# SD.net
KiCad netlist of a schematic drawn in Altium Designer
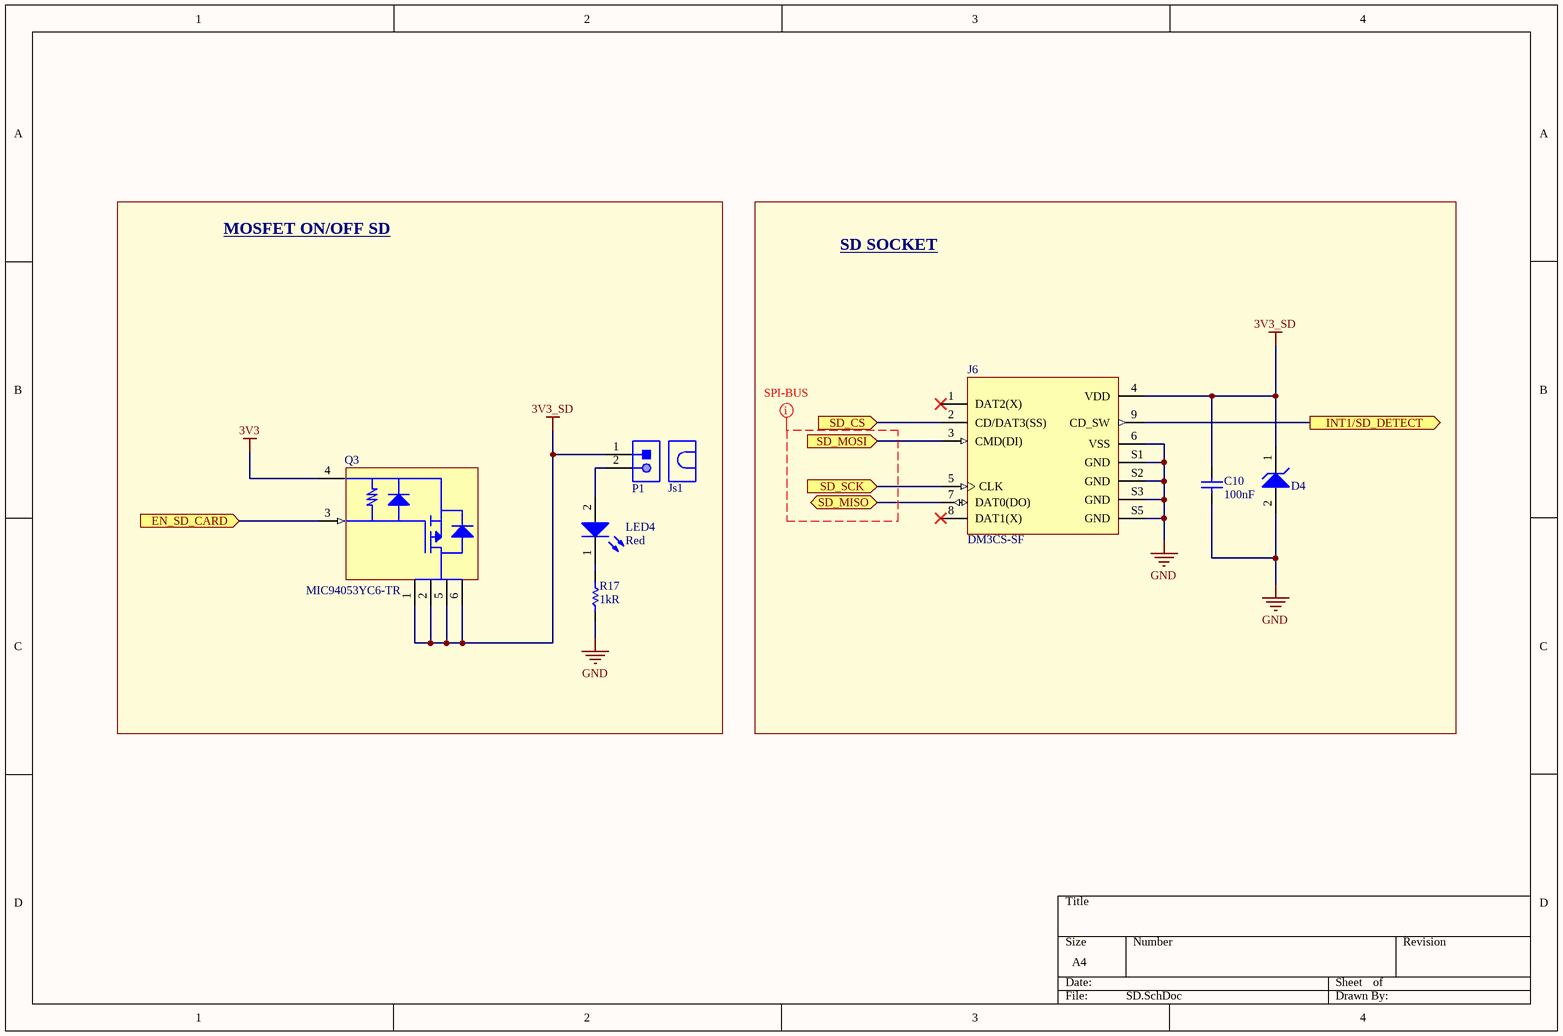
[diagram p0: SD.SchDoc]

(export (version "E")
  (design (tool "Eeschema 10.0.6"))
  (components
    (comp (ref "C10")
      (value "100nF")
      (footprint "Cap 0805 (2012 Metric)")
      (fields
        (field (name "MANUFACTURER") "Yageo")
        (field (name "MANUFACTURER PART NUMBER") "CC0805ZRY5V9BB104")
        (field (name "TOLERANCE") "80%")
      )
      (libsource (lib "Daniel_Integrated_Library") (part "Capacitor"))
    )
    (comp (ref "D4")
      (value "Diode")
      (footprint "Diode SOD123")
      (description "DIODE GEN PURP 75V 150MA 0603")
      (fields
        (field (name "MANUFACTURER") "Taiwan Semiconductor")
        (field (name "MANUFACTURER PART NUMBER") "TS4148CRZG")
      )
      (libsource (lib "Daniel_Integrated_Library") (part "Diode"))
    )
    (comp (ref "J6")
      (value "DM3CS-SF")
      (footprint "SDHolder")
      (description "10 (8 + 2) Position Card Connector Secure Digital - microSD™ Surface Mount, Right Angle Gold")
      (fields (field (name "MANUFACTURER") "Hirose"))
      (libsource (lib "Daniel_Integrated_Library") (part "SDHolder"))
    )
    (comp (ref "Js1")
      (value "Jumper (2x1)")
      (footprint "Header JMP 2x1")
      (description "2 (1 x 2) Position Shunt Connector Black Open Top 0.100\" (2.54mm) Gold")
      (fields
        (field (name "MANUFACTURER") "Sullins")
        (field (name "MANUFACTURER PART NUMBER") "QPC02SXGN-RC")
      )
      (libsource (lib "Daniel_Integrated_Library") (part "Jumper (2x1)"))
    )
    (comp (ref "LED4")
      (value "Red")
      (footprint "LED 0805(2012 METRIC)")
      (description "SMD LED red 2.4 V 0805, 150080RS75000, Würth Elektronik")
      (fields
        (field (name "MANUFACTURER") "Wurth Electronics")
        (field (name "MANUFACTURER PART NUMBER") "150080RS75000")
      )
      (libsource (lib "Daniel_Integrated_Library") (part "LED"))
    )
    (comp (ref "P1")
      (value "Header 2x1")
      (footprint "Header 2x1")
      (description "Connector Header Through Hole 2 position 0.100\" (2.54mm)")
      (fields
        (field (name "MANUFACTURER") "Amphenol FCI")
        (field (name "MANUFACTURER PART NUMBER") "68001-402HLF")
      )
      (libsource (lib "Daniel_Integrated_Library") (part "Header 2x1"))
    )
    (comp (ref "Q3")
      (value "MIC94053YC6-TR")
      (footprint "SC-70-6")
      (description "P-Channel 6V 2A (Ta) 270mW (Ta) Surface Mount SC-70-6")
      (fields (field (name "MANUFACTURER") "Microchip"))
      (libsource (lib "Daniel_Integrated_Library") (part "TransistorMosfet(Load)"))
    )
    (comp (ref "R17")
      (value "1kR")
      (footprint "Res 0805 (2012 Metric)")
      (description "RES 1K OHM 1% 1/4W 0805")
      (fields
        (field (name "MANUFACTURER") "Stackpole Electronics")
        (field (name "MANUFACTURER PART NUMBER") "RNCP0805FTD1K00")
      )
      (libsource (lib "Daniel_Integrated_Library") (part "Resistor"))
    )
  )
  (nets
    (net (code "1") (name "/EN_SD_CARD") (class "Default")
      (node (ref "Q3") (pin "3") (pinfunction "G_3") (pintype "input"))
    )
    (net (code "2") (name "/INT1{slash}SD_DETECT") (class "Default")
      (node (ref "J6") (pin "9") (pinfunction "CD_SW_9") (pintype "output"))
    )
    (net (code "3") (name "/SD_CS") (class "Default")
      (node (ref "J6") (pin "2") (pinfunction "CD/DAT3(SS)_2") (pintype "passive"))
    )
    (net (code "4") (name "/SD_MISO") (class "Default")
      (node (ref "J6") (pin "7") (pinfunction "DAT0(DO)_7") (pintype "bidirectional"))
    )
    (net (code "5") (name "/SD_MOSI") (class "Default")
      (node (ref "J6") (pin "3") (pinfunction "CMD(DI)_3") (pintype "input"))
    )
    (net (code "6") (name "/SD_SCK") (class "Default")
      (node (ref "J6") (pin "5") (pinfunction "CLK_5") (pintype "input"))
    )
    (net (code "7") (name "3V3") (class "Default")
      (node (ref "Q3") (pin "4") (pinfunction "S_4") (pintype "passive"))
    )
    (net (code "8") (name "3V3_SD") (class "Default")
      (node (ref "C10") (pin "1") (pinfunction "1_1") (pintype "passive"))
      (node (ref "D4") (pin "1") (pinfunction "K_1") (pintype "passive"))
      (node (ref "J6") (pin "4") (pinfunction "VDD_4") (pintype "passive"))
      (node (ref "P1") (pin "1") (pinfunction "1_1") (pintype "passive"))
      (node (ref "Q3") (pin "1") (pinfunction "D_1") (pintype "passive"))
      (node (ref "Q3") (pin "2") (pinfunction "D_2") (pintype "passive"))
      (node (ref "Q3") (pin "5") (pinfunction "D_5") (pintype "passive"))
      (node (ref "Q3") (pin "6") (pinfunction "D_6") (pintype "passive"))
    )
    (net (code "9") (name "GND") (class "Default")
      (node (ref "C10") (pin "2") (pinfunction "2_2") (pintype "passive"))
      (node (ref "D4") (pin "2") (pinfunction "A_2") (pintype "passive"))
      (node (ref "J6") (pin "6") (pinfunction "VSS_6") (pintype "passive"))
      (node (ref "J6") (pin "S1") (pinfunction "GND_S1") (pintype "passive"))
      (node (ref "J6") (pin "S2") (pinfunction "GND_S2") (pintype "passive"))
      (node (ref "J6") (pin "S3") (pinfunction "GND_S3") (pintype "passive"))
      (node (ref "J6") (pin "S5") (pinfunction "GND_S5") (pintype "passive"))
      (node (ref "R17") (pin "2") (pinfunction "2_2") (pintype "passive"))
    )
    (net (code "10") (name "Net-(LED4-A)") (class "Default")
      (node (ref "LED4") (pin "2") (pinfunction "A_2") (pintype "passive"))
      (node (ref "P1") (pin "2") (pinfunction "2_2") (pintype "passive"))
    )
    (net (code "11") (name "Net-(LED4-K)") (class "Default")
      (node (ref "LED4") (pin "1") (pinfunction "K_1") (pintype "passive"))
      (node (ref "R17") (pin "1") (pinfunction "1_1") (pintype "passive"))
    )
    (net (code "12") (name "unconnected-(J6-DAT1(X)-Pad8)") (class "Default")
      (node (ref "J6") (pin "8") (pinfunction "DAT1(X)_8") (pintype "passive+no_connect"))
    )
    (net (code "13") (name "unconnected-(J6-DAT2(X)-Pad1)") (class "Default")
      (node (ref "J6") (pin "1") (pinfunction "DAT2(X)_1") (pintype "passive+no_connect"))
    )
  )
)
